# Sheet1.net
KiCad netlist of a schematic drawn in Altium Designer
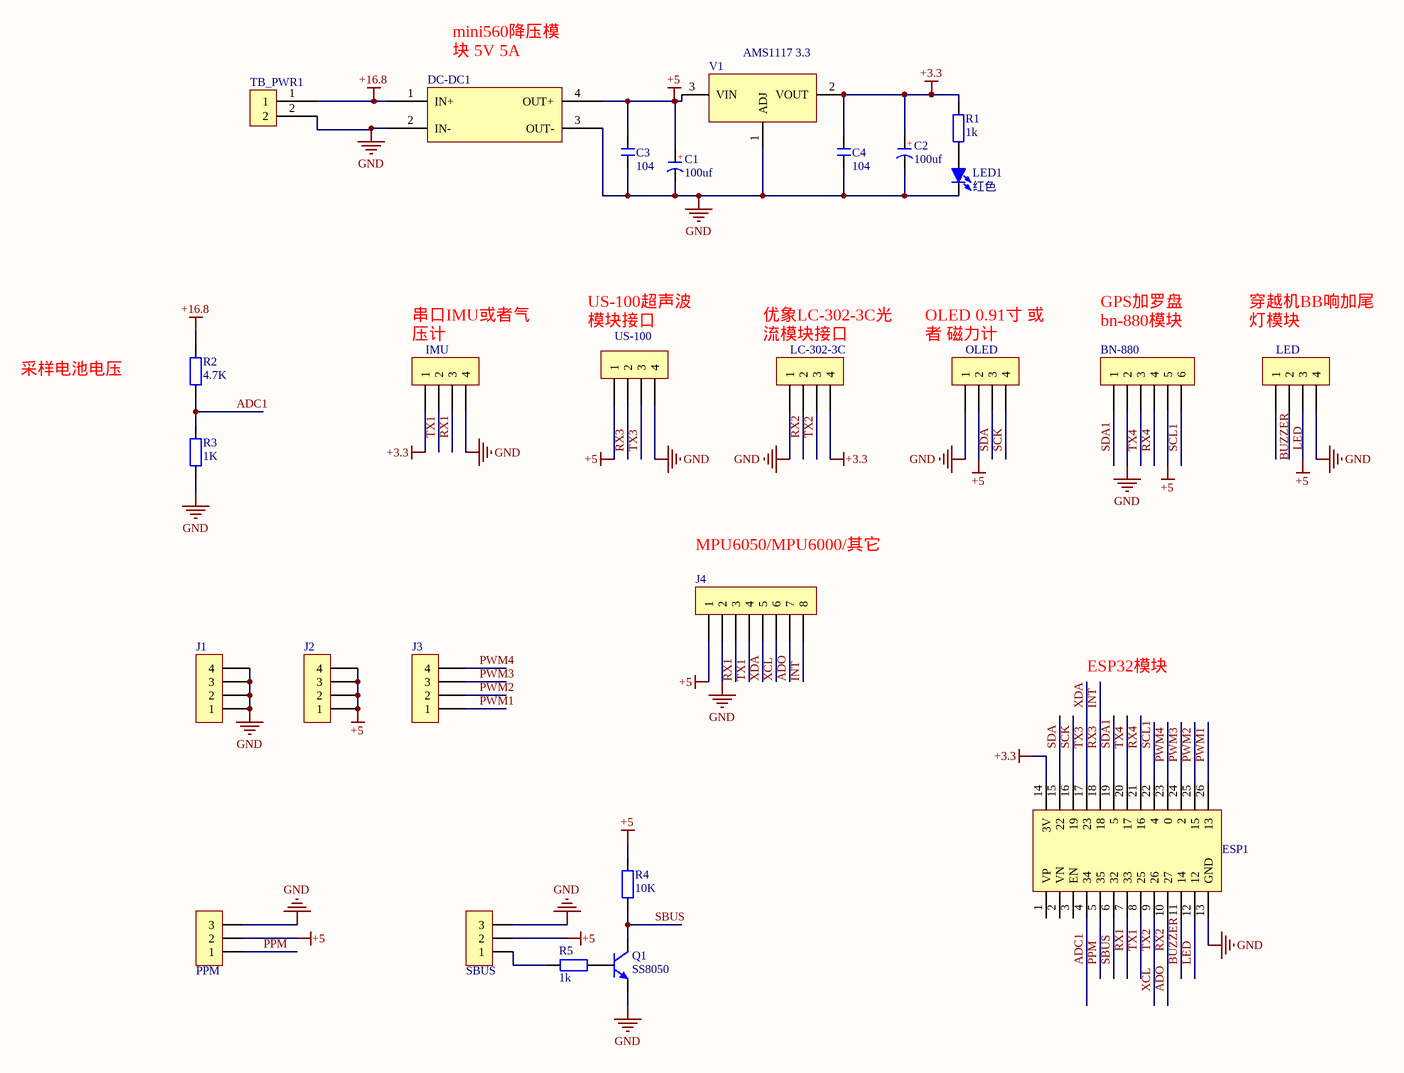
[diagram p0: Sheet1.SchDoc]

(export (version "E")
  (design (tool "Eeschema 10.0.6"))
  (components
    (comp (ref "BN-880")
      (value "Pin HDR1X6")
      (footprint "SH1.0 S-W-6P")
      (libsource (lib "排针") (part "Pin HDR1X6"))
    )
    (comp (ref "C1")
      (value "100uf")
      (footprint "C7343-D")
      (description "贴片钽电容")
      (fields (field (name "版权归属") "源创客"))
      (libsource (lib "3.1   - 电阻-电容-电感") (part "C-CD"))
    )
    (comp (ref "C2")
      (value "100uf")
      (footprint "C7343-D")
      (description "贴片钽电容")
      (fields (field (name "版权归属") "源创客"))
      (libsource (lib "3.1   - 电阻-电容-电感") (part "C-CD"))
    )
    (comp (ref "C3")
      (value "104")
      (footprint "C 0603_M")
      (description "无极性贴片电容")
      (fields (field (name "版权归属") "源创客"))
      (libsource (lib "3.1   - 电阻-电容-电感") (part "C"))
    )
    (comp (ref "C4")
      (value "104")
      (footprint "C 0603_M")
      (description "无极性贴片电容")
      (fields (field (name "版权归属") "源创客"))
      (libsource (lib "3.1   - 电阻-电容-电感") (part "C"))
    )
    (comp (ref "DC-DC1") (value "DC-DC") (footprint "DC-DC") (libsource (lib "Schlib1") (part "DC-DC")))
    (comp (ref "ESP1") (value "ESP32") (footprint "esp32") (libsource (lib "Schlib1") (part "ESP32")))
    (comp (ref "IMU")
      (value "Female HDR1X4")
      (footprint "SH1.0 S-W-4P")
      (libsource (lib "排母") (part "Female HDR1X4"))
    )
    (comp (ref "J1")
      (value "Pin HDR1X4")
      (footprint "Pin HDR1X4/2.54mm-S")
      (libsource (lib "排针") (part "Pin HDR1X4"))
    )
    (comp (ref "J2")
      (value "Pin HDR1X4")
      (footprint "Pin HDR1X4/2.54mm-S")
      (libsource (lib "排针") (part "Pin HDR1X4"))
    )
    (comp (ref "J3")
      (value "Pin HDR1X4")
      (footprint "Pin HDR1X4/2.54mm-S")
      (libsource (lib "排针") (part "Pin HDR1X4"))
    )
    (comp (ref "J4")
      (value "Female HDR1X8")
      (footprint "Fe-HDR1X8/2.54-S")
      (libsource (lib "排母") (part "Female HDR1X8"))
    )
    (comp (ref "LC-302-3C")
      (value "Female HDR1X4")
      (footprint "SH1.0 S-W-4P")
      (libsource (lib "排母") (part "Female HDR1X4"))
    )
    (comp (ref "LED")
      (value "Female HDR1X4")
      (footprint "SH1.0 S-W-4P")
      (libsource (lib "排母") (part "Female HDR1X4"))
    )
    (comp (ref "LED1")
      (value "红色")
      (footprint "LED 0603R")
      (description "方形LED")
      (fields (field (name "版权归属") "源创客"))
      (libsource (lib "9.1   - LED") (part "LED-F234"))
    )
    (comp (ref "OLED")
      (value "Female HDR1X4")
      (footprint "SH1.0 S-W-4P")
      (libsource (lib "排母") (part "Female HDR1X4"))
    )
    (comp (ref "PPM")
      (value "HDR-1X3")
      (footprint "Pin HDR1X3/2.54mm-S")
      (description "3P接插件")
      (fields (field (name "版权归属") "源创客"))
      (libsource (lib "4.10 - 接插件-脚距5.0") (part "Header 3"))
    )
    (comp (ref "Q1")
      (value "SS8050")
      (footprint "SOT23-3L")
      (description "高频放大-NPN型")
      (fields (field (name "版权归属") "源创客"))
      (libsource (lib "三极管B") (part "8050-SMD"))
    )
    (comp (ref "R1")
      (value "1k")
      (footprint "R 0603_M")
      (description "贴片电阻")
      (fields (field (name "版权归属") "源创客"))
      (libsource (lib "3.1   - 电阻-电容-电感") (part "R"))
    )
    (comp (ref "R2")
      (value "4.7K")
      (footprint "R 0603_M")
      (description "贴片电阻")
      (fields (field (name "版权归属") "源创客"))
      (libsource (lib "3.1   - 电阻-电容-电感") (part "R"))
    )
    (comp (ref "R3")
      (value "1K")
      (footprint "R 0603_M")
      (description "贴片电阻")
      (fields (field (name "版权归属") "源创客"))
      (libsource (lib "3.1   - 电阻-电容-电感") (part "R"))
    )
    (comp (ref "R4")
      (value "10K")
      (footprint "R 0603_M")
      (description "贴片电阻")
      (fields (field (name "版权归属") "源创客"))
      (libsource (lib "3.1   - 电阻-电容-电感") (part "R"))
    )
    (comp (ref "R5")
      (value "1k")
      (footprint "R 0603_M")
      (description "贴片电阻")
      (fields (field (name "版权归属") "源创客"))
      (libsource (lib "3.1   - 电阻-电容-电感") (part "R"))
    )
    (comp (ref "SBUS")
      (value "HDR-1X3")
      (footprint "Pin HDR1X3/2.54mm-S")
      (description "3P接插件")
      (fields (field (name "版权归属") "源创客"))
      (libsource (lib "4.10 - 接插件-脚距5.0") (part "Header 3"))
    )
    (comp (ref "TB_PWR1")
      (value "TB002-500-02BE")
      (footprint "XH2.54-LI-2P")
      (libsource (lib "ArduinoFOC") (part "TB002-500-02BE"))
    )
    (comp (ref "US-100")
      (value "Female HDR1X4")
      (footprint "SH1.0 S-W-4P")
      (libsource (lib "排母") (part "Female HDR1X4"))
    )
    (comp (ref "V1")
      (value "AMS1117 3.3")
      (footprint "SOT223")
      (description "可调线性稳压芯片")
      (fields (field (name "版权归属") "源创客"))
      (libsource (lib "1.3   - 电源类芯片") (part "LM317"))
    )
  )
  (nets
    (net (code "1") (name "+3.3") (class "Default")
      (node (ref "C2") (pin "1") (pinfunction "A_1") (pintype "passive"))
      (node (ref "C4") (pin "2") (pinfunction "2_2") (pintype "passive"))
      (node (ref "ESP1") (pin "14") (pinfunction "3V_14") (pintype "passive"))
      (node (ref "IMU") (pin "1") (pinfunction "1_1") (pintype "passive"))
      (node (ref "LC-302-3C") (pin "4") (pinfunction "4_4") (pintype "passive"))
      (node (ref "R1") (pin "2") (pinfunction "2_2") (pintype "passive"))
      (node (ref "V1") (pin "2") (pinfunction "VOUT_2") (pintype "passive"))
    )
    (net (code "2") (name "+5") (class "Default")
      (node (ref "BN-880") (pin "5") (pinfunction "5_5") (pintype "passive"))
      (node (ref "C1") (pin "1") (pinfunction "A_1") (pintype "passive"))
      (node (ref "C3") (pin "2") (pinfunction "2_2") (pintype "passive"))
      (node (ref "DC-DC1") (pin "4") (pinfunction "OUT+_4") (pintype "passive"))
      (node (ref "J2") (pin "1") (pinfunction "1_1") (pintype "passive"))
      (node (ref "J2") (pin "2") (pinfunction "2_2") (pintype "passive"))
      (node (ref "J2") (pin "3") (pinfunction "3_3") (pintype "passive"))
      (node (ref "J2") (pin "4") (pinfunction "4_4") (pintype "passive"))
      (node (ref "J4") (pin "1") (pinfunction "1_1") (pintype "passive"))
      (node (ref "LED") (pin "3") (pinfunction "3_3") (pintype "passive"))
      (node (ref "OLED") (pin "2") (pinfunction "2_2") (pintype "passive"))
      (node (ref "PPM") (pin "2") (pinfunction "2_2") (pintype "passive"))
      (node (ref "R4") (pin "1") (pinfunction "1_1") (pintype "passive"))
      (node (ref "SBUS") (pin "2") (pinfunction "2_2") (pintype "passive"))
      (node (ref "US-100") (pin "1") (pinfunction "1_1") (pintype "passive"))
      (node (ref "V1") (pin "3") (pinfunction "VIN_3") (pintype "passive"))
    )
    (net (code "3") (name "+16.8") (class "Default")
      (node (ref "DC-DC1") (pin "1") (pinfunction "IN+_1") (pintype "passive"))
      (node (ref "R2") (pin "2") (pinfunction "2_2") (pintype "passive"))
      (node (ref "TB_PWR1") (pin "1") (pinfunction "1_1") (pintype "passive"))
    )
    (net (code "4") (name "/ADC1") (class "Default")
      (node (ref "ESP1") (pin "4") (pinfunction "34_4") (pintype "passive"))
      (node (ref "R2") (pin "1") (pinfunction "1_1") (pintype "passive"))
      (node (ref "R3") (pin "2") (pinfunction "2_2") (pintype "passive"))
    )
    (net (code "5") (name "/ADO") (class "Default")
      (node (ref "ESP1") (pin "10") (pinfunction "27_10") (pintype "passive"))
      (node (ref "J4") (pin "7") (pinfunction "7_7") (pintype "passive"))
      (node (ref "LC-302-3C") (pin "2") (pinfunction "2_2") (pintype "passive"))
    )
    (net (code "6") (name "/BUZZER") (class "Default")
      (node (ref "ESP1") (pin "11") (pinfunction "14_11") (pintype "passive"))
      (node (ref "LED") (pin "1") (pinfunction "1_1") (pintype "passive"))
    )
    (net (code "7") (name "/INT") (class "Default")
      (node (ref "ESP1") (pin "18") (pinfunction "18_18") (pintype "passive"))
      (node (ref "J4") (pin "8") (pinfunction "8_8") (pintype "passive"))
      (node (ref "US-100") (pin "2") (pinfunction "2_2") (pintype "passive"))
    )
    (net (code "8") (name "/LED") (class "Default")
      (node (ref "ESP1") (pin "12") (pinfunction "12_12") (pintype "passive"))
      (node (ref "LED") (pin "2") (pinfunction "2_2") (pintype "passive"))
    )
    (net (code "9") (name "/PPM") (class "Default")
      (node (ref "ESP1") (pin "5") (pinfunction "35_5") (pintype "passive"))
      (node (ref "PPM") (pin "1") (pinfunction "1_1") (pintype "passive"))
    )
    (net (code "10") (name "/PWM1") (class "Default")
      (node (ref "ESP1") (pin "26") (pinfunction "13_26") (pintype "passive"))
      (node (ref "J3") (pin "1") (pinfunction "1_1") (pintype "passive"))
    )
    (net (code "11") (name "/PWM2") (class "Default")
      (node (ref "ESP1") (pin "25") (pinfunction "15_25") (pintype "passive"))
      (node (ref "J3") (pin "2") (pinfunction "2_2") (pintype "passive"))
    )
    (net (code "12") (name "/PWM3") (class "Default")
      (node (ref "ESP1") (pin "24") (pinfunction "2_24") (pintype "passive"))
      (node (ref "J3") (pin "3") (pinfunction "3_3") (pintype "passive"))
    )
    (net (code "13") (name "/PWM4") (class "Default")
      (node (ref "ESP1") (pin "23") (pinfunction "0_23") (pintype "passive"))
      (node (ref "J3") (pin "4") (pinfunction "4_4") (pintype "passive"))
    )
    (net (code "14") (name "/RX1") (class "Default")
      (node (ref "ESP1") (pin "7") (pinfunction "33_7") (pintype "passive"))
      (node (ref "IMU") (pin "3") (pinfunction "3_3") (pintype "passive"))
      (node (ref "J4") (pin "3") (pinfunction "3_3") (pintype "passive"))
    )
    (net (code "15") (name "/RX4") (class "Default")
      (node (ref "BN-880") (pin "4") (pinfunction "4_4") (pintype "passive"))
      (node (ref "ESP1") (pin "21") (pinfunction "16_21") (pintype "passive"))
    )
    (net (code "16") (name "/SBUS") (class "Default")
      (node (ref "ESP1") (pin "6") (pinfunction "32_6") (pintype "passive"))
      (node (ref "Q1") (pin "3") (pinfunction "C_3") (pintype "passive"))
      (node (ref "R4") (pin "2") (pinfunction "2_2") (pintype "passive"))
    )
    (net (code "17") (name "/SCK") (class "Default")
      (node (ref "ESP1") (pin "16") (pinfunction "19_16") (pintype "passive"))
      (node (ref "OLED") (pin "4") (pinfunction "4_4") (pintype "passive"))
    )
    (net (code "18") (name "/SCL1") (class "Default")
      (node (ref "BN-880") (pin "6") (pinfunction "6_6") (pintype "passive"))
      (node (ref "ESP1") (pin "22") (pinfunction "4_22") (pintype "passive"))
    )
    (net (code "19") (name "/SDA") (class "Default")
      (node (ref "ESP1") (pin "15") (pinfunction "22_15") (pintype "passive"))
      (node (ref "OLED") (pin "3") (pinfunction "3_3") (pintype "passive"))
    )
    (net (code "20") (name "/SDA1") (class "Default")
      (node (ref "BN-880") (pin "1") (pinfunction "1_1") (pintype "passive"))
      (node (ref "ESP1") (pin "19") (pinfunction "5_19") (pintype "passive"))
    )
    (net (code "21") (name "/TX1") (class "Default")
      (node (ref "ESP1") (pin "8") (pinfunction "25_8") (pintype "passive"))
      (node (ref "IMU") (pin "2") (pinfunction "2_2") (pintype "passive"))
      (node (ref "J4") (pin "4") (pinfunction "4_4") (pintype "passive"))
    )
    (net (code "22") (name "/TX2") (class "Default")
      (node (ref "ESP1") (pin "9") (pinfunction "26_9") (pintype "passive"))
      (node (ref "J4") (pin "6") (pinfunction "6_6") (pintype "passive"))
      (node (ref "LC-302-3C") (pin "3") (pinfunction "3_3") (pintype "passive"))
    )
    (net (code "23") (name "/TX3") (class "Default")
      (node (ref "ESP1") (pin "17") (pinfunction "23_17") (pintype "passive"))
      (node (ref "J4") (pin "5") (pinfunction "5_5") (pintype "passive"))
      (node (ref "US-100") (pin "3") (pinfunction "3_3") (pintype "passive"))
    )
    (net (code "24") (name "/TX4") (class "Default")
      (node (ref "BN-880") (pin "3") (pinfunction "3_3") (pintype "passive"))
      (node (ref "ESP1") (pin "20") (pinfunction "17_20") (pintype "passive"))
    )
    (net (code "25") (name "GND") (class "Default")
      (node (ref "BN-880") (pin "2") (pinfunction "2_2") (pintype "passive"))
      (node (ref "C1") (pin "2") (pinfunction "K_2") (pintype "passive"))
      (node (ref "C2") (pin "2") (pinfunction "K_2") (pintype "passive"))
      (node (ref "C3") (pin "1") (pinfunction "1_1") (pintype "passive"))
      (node (ref "C4") (pin "1") (pinfunction "1_1") (pintype "passive"))
      (node (ref "DC-DC1") (pin "2") (pinfunction "IN-_2") (pintype "passive"))
      (node (ref "DC-DC1") (pin "3") (pinfunction "OUT-_3") (pintype "passive"))
      (node (ref "ESP1") (pin "13") (pinfunction "GND_13") (pintype "passive"))
      (node (ref "IMU") (pin "4") (pinfunction "4_4") (pintype "passive"))
      (node (ref "J1") (pin "1") (pinfunction "1_1") (pintype "passive"))
      (node (ref "J1") (pin "2") (pinfunction "2_2") (pintype "passive"))
      (node (ref "J1") (pin "3") (pinfunction "3_3") (pintype "passive"))
      (node (ref "J1") (pin "4") (pinfunction "4_4") (pintype "passive"))
      (node (ref "J4") (pin "2") (pinfunction "2_2") (pintype "passive"))
      (node (ref "LC-302-3C") (pin "1") (pinfunction "1_1") (pintype "passive"))
      (node (ref "LED") (pin "4") (pinfunction "4_4") (pintype "passive"))
      (node (ref "LED1") (pin "2") (pinfunction "K_2") (pintype "passive"))
      (node (ref "OLED") (pin "1") (pinfunction "1_1") (pintype "passive"))
      (node (ref "PPM") (pin "3") (pinfunction "3_3") (pintype "passive"))
      (node (ref "Q1") (pin "2") (pinfunction "E_2") (pintype "passive"))
      (node (ref "R3") (pin "1") (pinfunction "1_1") (pintype "passive"))
      (node (ref "SBUS") (pin "3") (pinfunction "3_3") (pintype "passive"))
      (node (ref "TB_PWR1") (pin "2") (pinfunction "2_2") (pintype "passive"))
      (node (ref "US-100") (pin "4") (pinfunction "4_4") (pintype "passive"))
      (node (ref "V1") (pin "1") (pinfunction "ADJ_1") (pintype "passive"))
    )
    (net (code "26") (name "Net-(LED1-A)") (class "Default")
      (node (ref "LED1") (pin "1") (pinfunction "A_1") (pintype "passive"))
      (node (ref "R1") (pin "1") (pinfunction "1_1") (pintype "passive"))
    )
    (net (code "27") (name "Net-(Q1-B)") (class "Default")
      (node (ref "Q1") (pin "1") (pinfunction "B_1") (pintype "passive"))
      (node (ref "R5") (pin "1") (pinfunction "1_1") (pintype "passive"))
    )
    (net (code "28") (name "Net-(R5-Pad2)") (class "Default")
      (node (ref "R5") (pin "2") (pinfunction "2_2") (pintype "passive"))
      (node (ref "SBUS") (pin "1") (pinfunction "1_1") (pintype "passive"))
    )
    (net (code "29") (name "unconnected-(ESP1-EN-Pad3)") (class "Default")
      (node (ref "ESP1") (pin "3") (pinfunction "EN_3") (pintype "passive"))
    )
    (net (code "30") (name "unconnected-(ESP1-VN-Pad2)") (class "Default")
      (node (ref "ESP1") (pin "2") (pinfunction "VN_2") (pintype "passive"))
    )
    (net (code "31") (name "unconnected-(ESP1-VP-Pad1)") (class "Default")
      (node (ref "ESP1") (pin "1") (pinfunction "VP_1") (pintype "passive"))
    )
  )
)
